# 2_0.net
KiCad netlist of a schematic drawn in Altium Designer
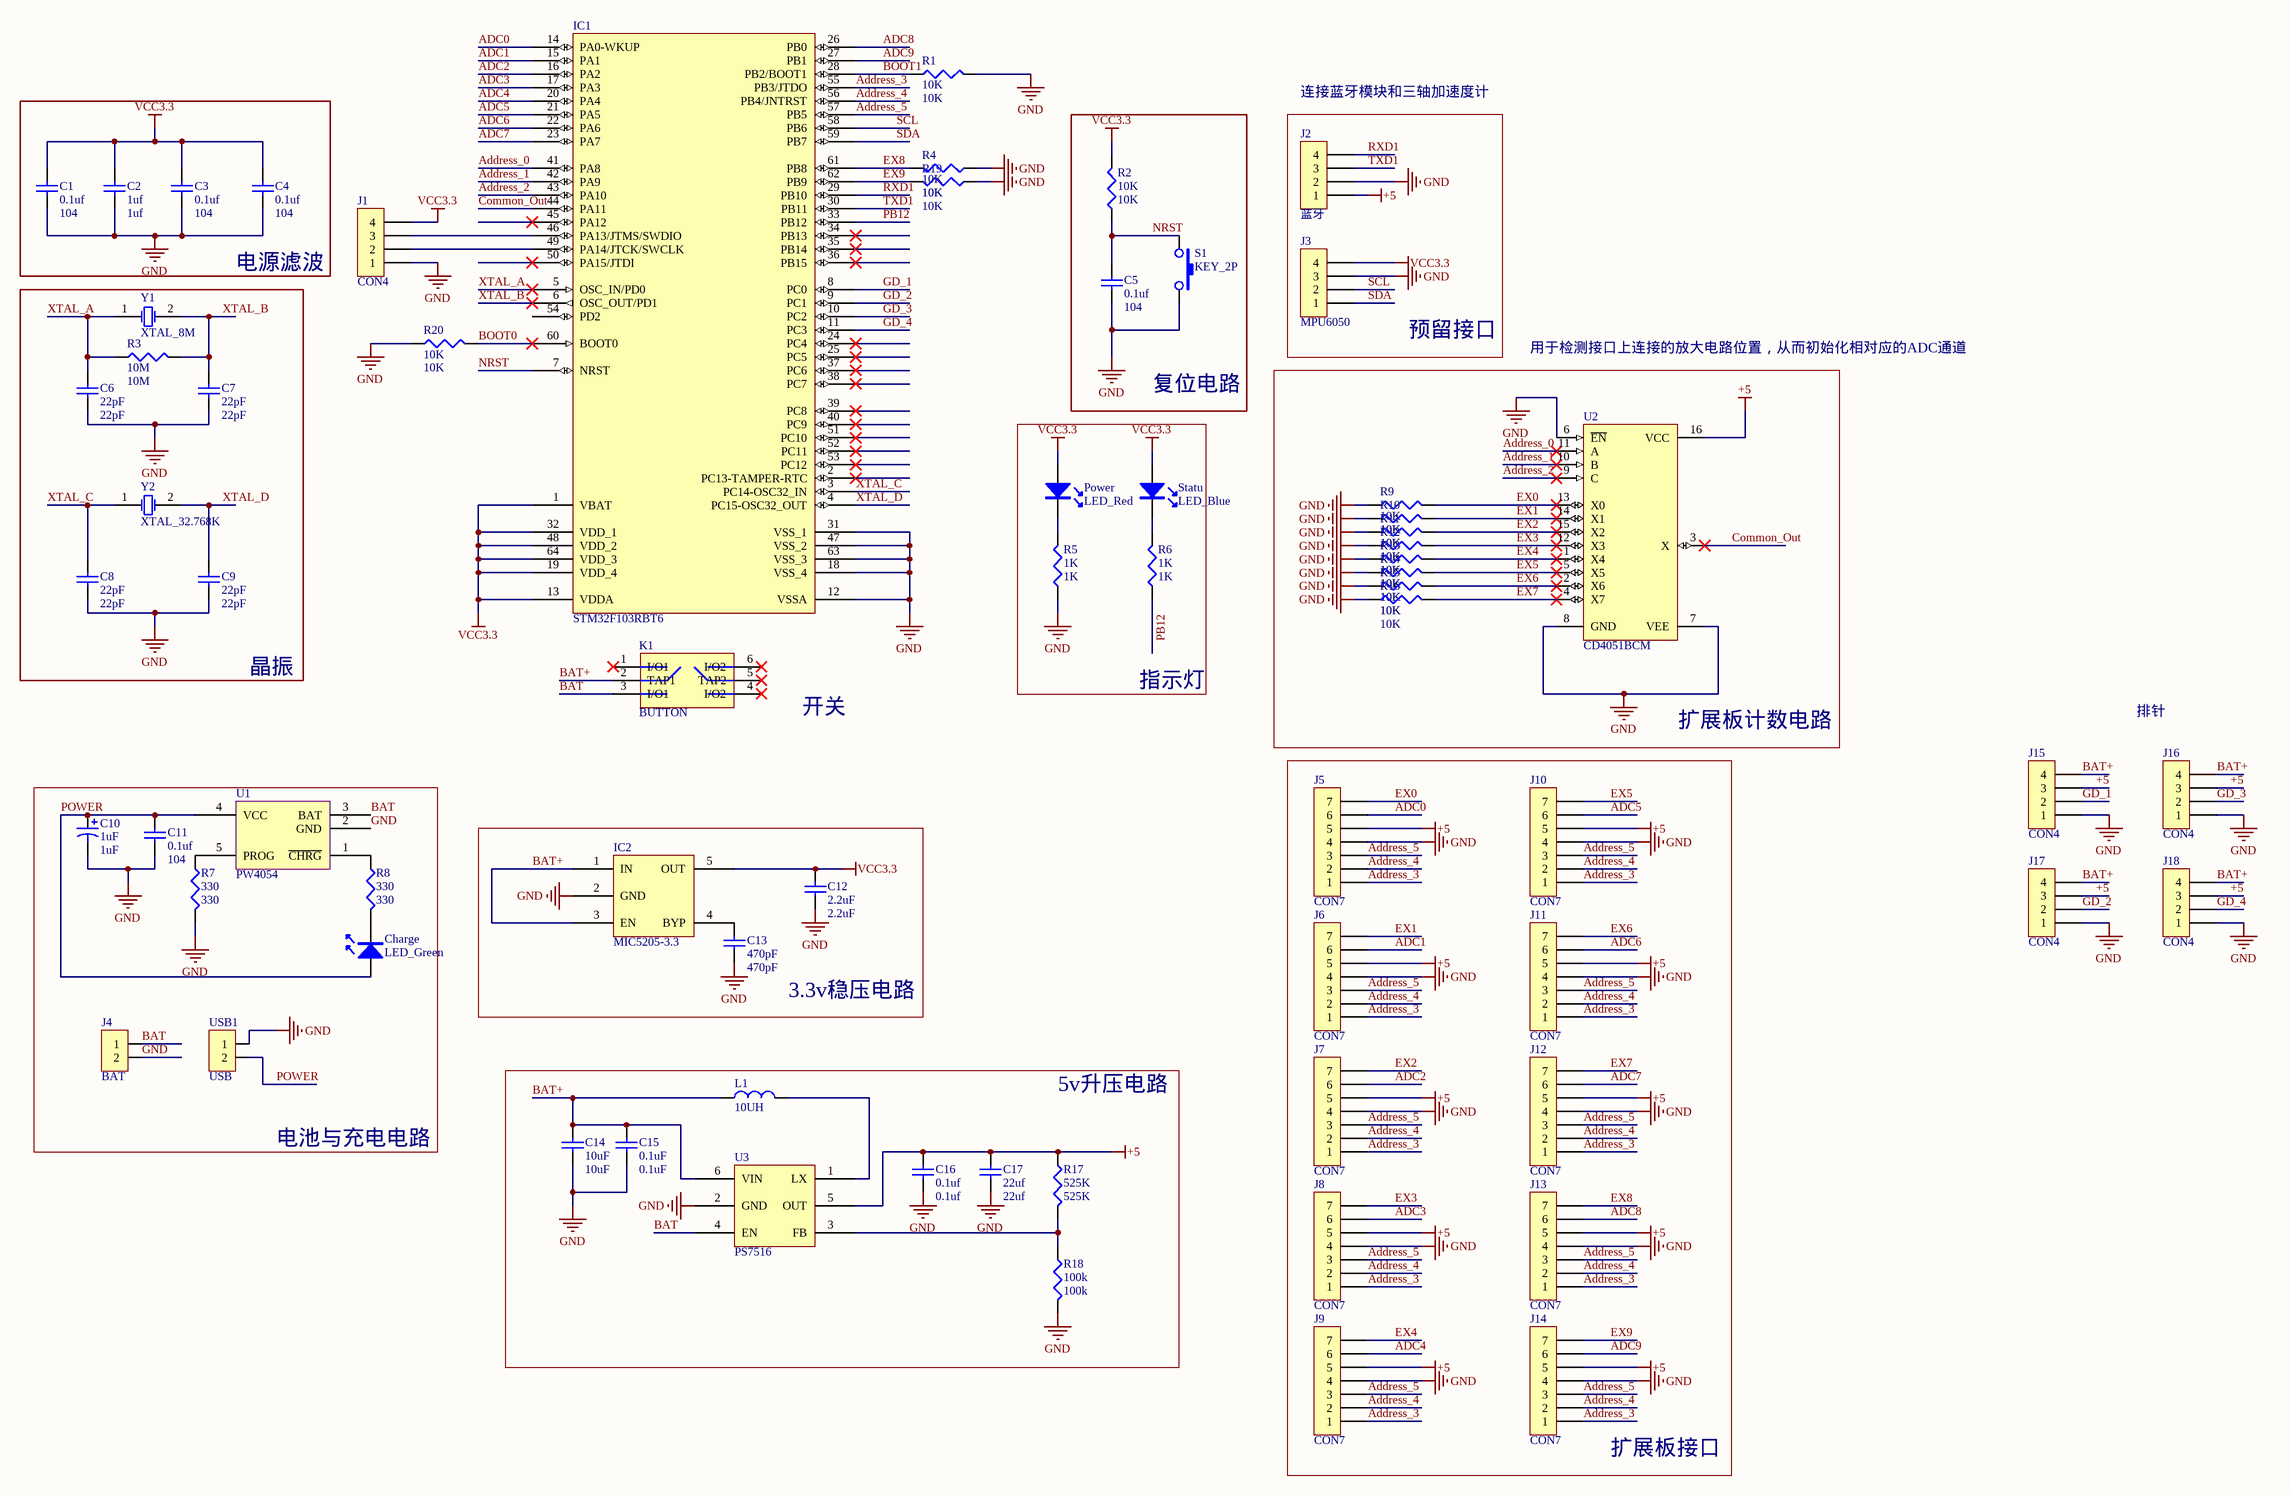
[diagram p0: 主控板原理图2.0.SchDoc]

(export (version "E")
  (design (tool "Eeschema 10.0.6"))
  (components
    (comp (ref "C1")
      (value "0.1uf")
      (footprint "6-0805_L")
      (description "Capacitor (Semiconductor SIM Model)")
      (fields (field (name "ALTIUM_VALUE") "104") (field (name "PUBLISHER") "Altium Limited"))
      (libsource (lib "Miscellaneous Devices") (part "Cap Semi"))
    )
    (comp (ref "C2")
      (value "1uf")
      (footprint "6-0805_L")
      (description "Capacitor (Semiconductor SIM Model)")
      (fields (field (name "ALTIUM_VALUE") "1uf") (field (name "PUBLISHER") "Altium Limited"))
      (libsource (lib "Miscellaneous Devices") (part "Cap Semi"))
    )
    (comp (ref "C3")
      (value "0.1uf")
      (footprint "6-0805_L")
      (description "Capacitor (Semiconductor SIM Model)")
      (fields (field (name "ALTIUM_VALUE") "104") (field (name "PUBLISHER") "Altium Limited"))
      (libsource (lib "Miscellaneous Devices") (part "Cap Semi"))
    )
    (comp (ref "C4")
      (value "0.1uf")
      (footprint "6-0805_L")
      (description "Capacitor (Semiconductor SIM Model)")
      (fields (field (name "ALTIUM_VALUE") "104") (field (name "PUBLISHER") "Altium Limited"))
      (libsource (lib "Miscellaneous Devices") (part "Cap Semi"))
    )
    (comp (ref "C5")
      (value "0.1uf")
      (footprint "6-0805_L")
      (description "Capacitor (Semiconductor SIM Model)")
      (fields (field (name "ALTIUM_VALUE") "104") (field (name "PUBLISHER") "Altium Limited"))
      (libsource (lib "Miscellaneous Devices") (part "Cap Semi"))
    )
    (comp (ref "C6")
      (value "22pF")
      (footprint "6-0805_L")
      (description "Capacitor (Semiconductor SIM Model)")
      (fields (field (name "ALTIUM_VALUE") "22pF") (field (name "PUBLISHER") "Altium Limited"))
      (libsource (lib "Miscellaneous Devices") (part "Cap Semi"))
    )
    (comp (ref "C7")
      (value "22pF")
      (footprint "6-0805_L")
      (description "Capacitor (Semiconductor SIM Model)")
      (fields (field (name "ALTIUM_VALUE") "22pF") (field (name "PUBLISHER") "Altium Limited"))
      (libsource (lib "Miscellaneous Devices") (part "Cap Semi"))
    )
    (comp (ref "C8")
      (value "22pF")
      (footprint "6-0805_L")
      (description "Capacitor (Semiconductor SIM Model)")
      (fields (field (name "ALTIUM_VALUE") "22pF") (field (name "PUBLISHER") "Altium Limited"))
      (libsource (lib "Miscellaneous Devices") (part "Cap Semi"))
    )
    (comp (ref "C9")
      (value "22pF")
      (footprint "6-0805_L")
      (description "Capacitor (Semiconductor SIM Model)")
      (fields (field (name "ALTIUM_VALUE") "22pF") (field (name "PUBLISHER") "Altium Limited"))
      (libsource (lib "Miscellaneous Devices") (part "Cap Semi"))
    )
    (comp (ref "C10")
      (value "1uF")
      (footprint "C0805")
      (description "Polarized Capacitor (Surface Mount)")
      (fields (field (name "ALTIUM_VALUE") "1uF") (field (name "PUBLISHER") "Altium Limited"))
      (libsource (lib "Miscellaneous Devices") (part "Cap Pol3"))
    )
    (comp (ref "C11")
      (value "0.1uf")
      (footprint "6-0805_L")
      (description "Capacitor (Semiconductor SIM Model)")
      (fields (field (name "ALTIUM_VALUE") "104") (field (name "PUBLISHER") "Altium Limited"))
      (libsource (lib "Miscellaneous Devices") (part "Cap Semi"))
    )
    (comp (ref "C12")
      (value "2.2uF")
      (footprint "6-0805_L")
      (description "Capacitor (Semiconductor SIM Model)")
      (fields (field (name "ALTIUM_VALUE") "2.2uF") (field (name "PUBLISHER") "Altium Limited"))
      (libsource (lib "Miscellaneous Devices") (part "Cap Semi"))
    )
    (comp (ref "C13")
      (value "470pF")
      (footprint "6-0805_L")
      (description "Capacitor (Semiconductor SIM Model)")
      (fields (field (name "ALTIUM_VALUE") "470pF") (field (name "PUBLISHER") "Altium Limited"))
      (libsource (lib "Miscellaneous Devices") (part "Cap Semi"))
    )
    (comp (ref "C14")
      (value "10uF")
      (footprint "6-0805_L")
      (description "Capacitor (Semiconductor SIM Model)")
      (fields (field (name "ALTIUM_VALUE") "10uF") (field (name "PUBLISHER") "Altium Limited"))
      (libsource (lib "Miscellaneous Devices") (part "Cap Semi"))
    )
    (comp (ref "C15")
      (value "0.1uF")
      (footprint "6-0805_L")
      (description "Capacitor (Semiconductor SIM Model)")
      (fields (field (name "ALTIUM_VALUE") "0.1uF") (field (name "PUBLISHER") "Altium Limited"))
      (libsource (lib "Miscellaneous Devices") (part "Cap Semi"))
    )
    (comp (ref "C16")
      (value "0.1uf")
      (footprint "6-0805_L")
      (description "Capacitor (Semiconductor SIM Model)")
      (fields (field (name "ALTIUM_VALUE") "0.1uf") (field (name "PUBLISHER") "Altium Limited"))
      (libsource (lib "Miscellaneous Devices") (part "Cap Semi"))
    )
    (comp (ref "C17")
      (value "22uf")
      (footprint "6-0805_L")
      (description "Capacitor (Semiconductor SIM Model)")
      (fields (field (name "ALTIUM_VALUE") "22uf") (field (name "PUBLISHER") "Altium Limited"))
      (libsource (lib "Miscellaneous Devices") (part "Cap Semi"))
    )
    (comp (ref "Charge")
      (value "LED_Green")
      (footprint "6-0805_M")
      (description "LED")
      (libsource (lib "Component") (part "LED"))
    )
    (comp (ref "IC1")
      (value "STM32F103RBT6")
      (footprint "LQFP64_N")
      (description "STM32 ARM-based 32-bit MCU with 128 Kbytes Flash, 64-pin LQFP, Industrial Temperature")
      (fields (field (name "PUBLISHER") "Altium Limited"))
      (libsource (lib "ST Microcontroller 32-Bit STM32") (part "STM32F103RBT6"))
    )
    (comp (ref "IC2")
      (value "MIC5205-3.3")
      (footprint "SOT-23-5")
      (description "稳压")
      (libsource (lib "Chip") (part "MIC5205-3.3"))
    )
    (comp (ref "J1")
      (value "CON4")
      (footprint "HDR1X4")
      (description "连接器")
      (libsource (lib "Connector") (part "CON4"))
    )
    (comp (ref "J2")
      (value "蓝牙")
      (footprint "HDR1X4")
      (description "Connector")
      (libsource (lib "杂元件库") (part "CON4"))
    )
    (comp (ref "J3")
      (value "MPU6050")
      (footprint "HDR1X4")
      (description "Connector")
      (libsource (lib "杂元件库") (part "CON4"))
    )
    (comp (ref "J4")
      (value "BAT")
      (footprint "HDR1X2")
      (description "Conjunctor")
      (libsource (lib "zj") (part "CON2"))
    )
    (comp (ref "J5")
      (value "CON7")
      (footprint "8P软排线")
      (description "Connector")
      (libsource (lib "杂元件库") (part "CON7"))
    )
    (comp (ref "J6")
      (value "CON7")
      (footprint "8P软排线")
      (description "Connector")
      (libsource (lib "杂元件库") (part "CON7"))
    )
    (comp (ref "J7")
      (value "CON7")
      (footprint "8P软排线")
      (description "Connector")
      (libsource (lib "杂元件库") (part "CON7"))
    )
    (comp (ref "J8")
      (value "CON7")
      (footprint "8P软排线")
      (description "Connector")
      (libsource (lib "杂元件库") (part "CON7"))
    )
    (comp (ref "J9")
      (value "CON7")
      (footprint "8P软排线")
      (description "Connector")
      (libsource (lib "杂元件库") (part "CON7"))
    )
    (comp (ref "J10")
      (value "CON7")
      (footprint "8P软排线")
      (description "Connector")
      (libsource (lib "杂元件库") (part "CON7"))
    )
    (comp (ref "J11")
      (value "CON7")
      (footprint "8P软排线")
      (description "Connector")
      (libsource (lib "杂元件库") (part "CON7"))
    )
    (comp (ref "J12")
      (value "CON7")
      (footprint "8P软排线")
      (description "Connector")
      (libsource (lib "杂元件库") (part "CON7"))
    )
    (comp (ref "J13")
      (value "CON7")
      (footprint "8P软排线")
      (description "Connector")
      (libsource (lib "杂元件库") (part "CON7"))
    )
    (comp (ref "J14")
      (value "CON7")
      (footprint "8P软排线")
      (description "Connector")
      (libsource (lib "杂元件库") (part "CON7"))
    )
    (comp (ref "J15") (value "CON4") (description "Connector") (libsource (lib "杂元件库") (part "CON4")))
    (comp (ref "J16") (value "CON4") (description "Connector") (libsource (lib "杂元件库") (part "CON4")))
    (comp (ref "J17") (value "CON4") (description "Connector") (libsource (lib "杂元件库") (part "CON4")))
    (comp (ref "J18") (value "CON4") (description "Connector") (libsource (lib "杂元件库") (part "CON4")))
    (comp (ref "K1")
      (value "BUTTON")
      (footprint "My:switch")
      (description "自锁按键")
      (libsource (lib "Component") (part "BUTTON"))
    )
    (comp (ref "L1")
      (value "10UH")
      (footprint "0850")
      (description "电感")
      (libsource (lib "Component") (part "Inductor"))
    )
    (comp (ref "Power")
      (value "LED_Red")
      (footprint "6-0805_M")
      (description "LED")
      (libsource (lib "Component") (part "LED"))
    )
    (comp (ref "R1")
      (value "10K")
      (footprint "6-0805_L")
      (description "Resistor")
      (fields (field (name "ALTIUM_VALUE") "10K") (field (name "PUBLISHER") "Altium Limited"))
      (libsource (lib "Miscellaneous Devices") (part "Res3"))
    )
    (comp (ref "R2")
      (value "10K")
      (footprint "6-0805_L")
      (description "Resistor")
      (fields (field (name "ALTIUM_VALUE") "10K") (field (name "PUBLISHER") "Altium Limited"))
      (libsource (lib "Miscellaneous Devices") (part "Res3"))
    )
    (comp (ref "R3")
      (value "10M")
      (footprint "6-0805_L")
      (description "Resistor")
      (fields (field (name "ALTIUM_VALUE") "10M") (field (name "PUBLISHER") "Altium Limited"))
      (libsource (lib "Miscellaneous Devices") (part "Res3"))
    )
    (comp (ref "R4")
      (value "10K")
      (footprint "6-0805_L")
      (description "Resistor")
      (fields (field (name "ALTIUM_VALUE") "10K") (field (name "PUBLISHER") "Altium Limited"))
      (libsource (lib "Miscellaneous Devices") (part "Res3"))
    )
    (comp (ref "R5")
      (value "1K")
      (footprint "6-0805_L")
      (description "Resistor")
      (fields (field (name "ALTIUM_VALUE") "1K") (field (name "PUBLISHER") "Altium Limited"))
      (libsource (lib "Miscellaneous Devices") (part "Res3"))
    )
    (comp (ref "R6")
      (value "1K")
      (footprint "6-0805_L")
      (description "Resistor")
      (fields (field (name "ALTIUM_VALUE") "1K") (field (name "PUBLISHER") "Altium Limited"))
      (libsource (lib "Miscellaneous Devices") (part "Res3"))
    )
    (comp (ref "R7")
      (value "330")
      (footprint "6-0805_L")
      (description "Resistor")
      (fields (field (name "ALTIUM_VALUE") "330") (field (name "PUBLISHER") "Altium Limited"))
      (libsource (lib "Miscellaneous Devices") (part "Res3"))
    )
    (comp (ref "R8")
      (value "330")
      (footprint "6-0805_L")
      (description "Resistor")
      (fields (field (name "ALTIUM_VALUE") "330") (field (name "PUBLISHER") "Altium Limited"))
      (libsource (lib "Miscellaneous Devices") (part "Res3"))
    )
    (comp (ref "R9")
      (value "10K")
      (footprint "6-0805_L")
      (description "Resistor")
      (fields (field (name "ALTIUM_VALUE") "10K") (field (name "PUBLISHER") "Altium Limited"))
      (libsource (lib "Miscellaneous Devices") (part "Res3"))
    )
    (comp (ref "R10")
      (value "10K")
      (footprint "6-0805_L")
      (description "Resistor")
      (fields (field (name "ALTIUM_VALUE") "10K") (field (name "PUBLISHER") "Altium Limited"))
      (libsource (lib "Miscellaneous Devices") (part "Res3"))
    )
    (comp (ref "R11")
      (value "10K")
      (footprint "6-0805_L")
      (description "Resistor")
      (fields (field (name "ALTIUM_VALUE") "10K") (field (name "PUBLISHER") "Altium Limited"))
      (libsource (lib "Miscellaneous Devices") (part "Res3"))
    )
    (comp (ref "R12")
      (value "10K")
      (footprint "6-0805_L")
      (description "Resistor")
      (fields (field (name "ALTIUM_VALUE") "10K") (field (name "PUBLISHER") "Altium Limited"))
      (libsource (lib "Miscellaneous Devices") (part "Res3"))
    )
    (comp (ref "R13")
      (value "10K")
      (footprint "6-0805_L")
      (description "Resistor")
      (fields (field (name "ALTIUM_VALUE") "10K") (field (name "PUBLISHER") "Altium Limited"))
      (libsource (lib "Miscellaneous Devices") (part "Res3"))
    )
    (comp (ref "R14")
      (value "10K")
      (footprint "6-0805_L")
      (description "Resistor")
      (fields (field (name "ALTIUM_VALUE") "10K") (field (name "PUBLISHER") "Altium Limited"))
      (libsource (lib "Miscellaneous Devices") (part "Res3"))
    )
    (comp (ref "R15")
      (value "10K")
      (footprint "6-0805_L")
      (description "Resistor")
      (fields (field (name "ALTIUM_VALUE") "10K") (field (name "PUBLISHER") "Altium Limited"))
      (libsource (lib "Miscellaneous Devices") (part "Res3"))
    )
    (comp (ref "R16")
      (value "10K")
      (footprint "6-0805_L")
      (description "Resistor")
      (fields (field (name "ALTIUM_VALUE") "10K") (field (name "PUBLISHER") "Altium Limited"))
      (libsource (lib "Miscellaneous Devices") (part "Res3"))
    )
    (comp (ref "R17")
      (value "525K")
      (footprint "6-0805_L")
      (description "Resistor")
      (fields (field (name "ALTIUM_VALUE") "525K") (field (name "PUBLISHER") "Altium Limited"))
      (libsource (lib "Miscellaneous Devices") (part "Res3"))
    )
    (comp (ref "R18")
      (value "100k")
      (footprint "6-0805_L")
      (description "Resistor")
      (fields (field (name "ALTIUM_VALUE") "100k") (field (name "PUBLISHER") "Altium Limited"))
      (libsource (lib "Miscellaneous Devices") (part "Res3"))
    )
    (comp (ref "R19")
      (value "10K")
      (footprint "6-0805_L")
      (description "Resistor")
      (fields (field (name "ALTIUM_VALUE") "10K") (field (name "PUBLISHER") "Altium Limited"))
      (libsource (lib "Miscellaneous Devices") (part "Res3"))
    )
    (comp (ref "R20")
      (value "10K")
      (footprint "6-0805_L")
      (description "Resistor")
      (fields (field (name "ALTIUM_VALUE") "10K") (field (name "PUBLISHER") "Altium Limited"))
      (libsource (lib "Miscellaneous Devices") (part "Res3"))
    )
    (comp (ref "S1")
      (value "KEY_2P")
      (footprint "My:button")
      (description "轻触按键2P")
      (libsource (lib "Component") (part "KEY_2P"))
    )
    (comp (ref "Statu")
      (value "LED_Blue")
      (footprint "6-0805_M")
      (description "LED")
      (libsource (lib "Component") (part "LED"))
    )
    (comp (ref "U1") (value "PW4054") (footprint "SOT-23-CT5_L") (libsource (lib "Schlib") (part "PW4054")))
    (comp (ref "U2")
      (value "CD4051BCM")
      (footprint "M16A_N")
      (description "8-Channel Analog Multiplexer/Demultiplexer")
      (fields (field (name "PUBLISHER") "Altium Limited"))
      (libsource (lib "altium-import") (part "root_0_CD4051BCM_"))
    )
    (comp (ref "U3")
      (value "PS7516")
      (footprint "SOT23-6_M")
      (libsource (lib "Integrated_Library1") (part "PS7516"))
    )
    (comp (ref "USB1")
      (value "USB")
      (footprint "Type-C")
      (description "Conjunctor")
      (libsource (lib "zj") (part "CON2"))
    )
    (comp (ref "Y1")
      (value "XTAL_8M")
      (footprint "xtal")
      (description "Crystal Oscillator")
      (fields (field (name "PUBLISHER") "Altium Limited"))
      (libsource (lib "Miscellaneous Devices") (part "XTAL"))
    )
    (comp (ref "Y2")
      (value "XTAL_32.768K")
      (footprint "R38")
      (description "Crystal Oscillator")
      (fields (field (name "PUBLISHER") "Altium Limited"))
      (libsource (lib "Miscellaneous Devices") (part "XTAL"))
    )
  )
  (nets
    (net (code "1") (name "+5") (class "Default")
      (node (ref "C16") (pin "2") (pinfunction "2_2") (pintype "passive"))
      (node (ref "C17") (pin "2") (pinfunction "2_2") (pintype "passive"))
      (node (ref "J10") (pin "5") (pinfunction "5_5") (pintype "passive"))
      (node (ref "J11") (pin "5") (pinfunction "5_5") (pintype "passive"))
      (node (ref "J12") (pin "5") (pinfunction "5_5") (pintype "passive"))
      (node (ref "J13") (pin "5") (pinfunction "5_5") (pintype "passive"))
      (node (ref "J14") (pin "5") (pinfunction "5_5") (pintype "passive"))
      (node (ref "J15") (pin "3") (pinfunction "3_3") (pintype "passive"))
      (node (ref "J16") (pin "3") (pinfunction "3_3") (pintype "passive"))
      (node (ref "J17") (pin "3") (pinfunction "3_3") (pintype "passive"))
      (node (ref "J18") (pin "3") (pinfunction "3_3") (pintype "passive"))
      (node (ref "J2") (pin "1") (pinfunction "1_1") (pintype "passive"))
      (node (ref "J5") (pin "5") (pinfunction "5_5") (pintype "passive"))
      (node (ref "J6") (pin "5") (pinfunction "5_5") (pintype "passive"))
      (node (ref "J7") (pin "5") (pinfunction "5_5") (pintype "passive"))
      (node (ref "J8") (pin "5") (pinfunction "5_5") (pintype "passive"))
      (node (ref "J9") (pin "5") (pinfunction "5_5") (pintype "passive"))
      (node (ref "R17") (pin "1") (pinfunction "1_1") (pintype "passive"))
      (node (ref "U2") (pin "16") (pinfunction "VCC_16") (pintype "power_in"))
      (node (ref "U3") (pin "5") (pinfunction "OUT_5") (pintype "passive"))
    )
    (net (code "2") (name "/ADC0") (class "Default")
      (node (ref "IC1") (pin "14") (pinfunction "PA0-WKUP_14") (pintype "bidirectional"))
      (node (ref "J5") (pin "6") (pinfunction "6_6") (pintype "passive"))
    )
    (net (code "3") (name "/ADC1") (class "Default")
      (node (ref "IC1") (pin "15") (pinfunction "PA1_15") (pintype "bidirectional"))
      (node (ref "J6") (pin "6") (pinfunction "6_6") (pintype "passive"))
    )
    (net (code "4") (name "/ADC2") (class "Default")
      (node (ref "IC1") (pin "16") (pinfunction "PA2_16") (pintype "bidirectional"))
      (node (ref "J7") (pin "6") (pinfunction "6_6") (pintype "passive"))
    )
    (net (code "5") (name "/ADC3") (class "Default")
      (node (ref "IC1") (pin "17") (pinfunction "PA3_17") (pintype "bidirectional"))
      (node (ref "J8") (pin "6") (pinfunction "6_6") (pintype "passive"))
    )
    (net (code "6") (name "/ADC4") (class "Default")
      (node (ref "IC1") (pin "20") (pinfunction "PA4_20") (pintype "bidirectional"))
      (node (ref "J9") (pin "6") (pinfunction "6_6") (pintype "passive"))
    )
    (net (code "7") (name "/ADC5") (class "Default")
      (node (ref "IC1") (pin "21") (pinfunction "PA5_21") (pintype "bidirectional"))
      (node (ref "J10") (pin "6") (pinfunction "6_6") (pintype "passive"))
    )
    (net (code "8") (name "/ADC6") (class "Default")
      (node (ref "IC1") (pin "22") (pinfunction "PA6_22") (pintype "bidirectional"))
      (node (ref "J11") (pin "6") (pinfunction "6_6") (pintype "passive"))
    )
    (net (code "9") (name "/ADC7") (class "Default")
      (node (ref "IC1") (pin "23") (pinfunction "PA7_23") (pintype "bidirectional"))
      (node (ref "J12") (pin "6") (pinfunction "6_6") (pintype "passive"))
    )
    (net (code "10") (name "/ADC8") (class "Default")
      (node (ref "IC1") (pin "26") (pinfunction "PB0_26") (pintype "bidirectional"))
      (node (ref "J13") (pin "6") (pinfunction "6_6") (pintype "passive"))
    )
    (net (code "11") (name "/ADC9") (class "Default")
      (node (ref "IC1") (pin "27") (pinfunction "PB1_27") (pintype "bidirectional"))
      (node (ref "J14") (pin "6") (pinfunction "6_6") (pintype "passive"))
    )
    (net (code "12") (name "/Address_0") (class "Default")
      (node (ref "IC1") (pin "41") (pinfunction "PA8_41") (pintype "bidirectional"))
      (node (ref "U2") (pin "11") (pinfunction "A_11") (pintype "input"))
    )
    (net (code "13") (name "/Address_1") (class "Default")
      (node (ref "IC1") (pin "42") (pinfunction "PA9_42") (pintype "bidirectional"))
      (node (ref "U2") (pin "10") (pinfunction "B_10") (pintype "input"))
    )
    (net (code "14") (name "/Address_2") (class "Default")
      (node (ref "IC1") (pin "43") (pinfunction "PA10_43") (pintype "bidirectional"))
      (node (ref "U2") (pin "9") (pinfunction "C_9") (pintype "input"))
    )
    (net (code "15") (name "/Address_3") (class "Default")
      (node (ref "IC1") (pin "55") (pinfunction "PB3/JTDO_55") (pintype "bidirectional"))
      (node (ref "J10") (pin "1") (pinfunction "1_1") (pintype "passive"))
      (node (ref "J11") (pin "1") (pinfunction "1_1") (pintype "passive"))
      (node (ref "J12") (pin "1") (pinfunction "1_1") (pintype "passive"))
      (node (ref "J13") (pin "1") (pinfunction "1_1") (pintype "passive"))
      (node (ref "J14") (pin "1") (pinfunction "1_1") (pintype "passive"))
      (node (ref "J5") (pin "1") (pinfunction "1_1") (pintype "passive"))
      (node (ref "J6") (pin "1") (pinfunction "1_1") (pintype "passive"))
      (node (ref "J7") (pin "1") (pinfunction "1_1") (pintype "passive"))
      (node (ref "J8") (pin "1") (pinfunction "1_1") (pintype "passive"))
      (node (ref "J9") (pin "1") (pinfunction "1_1") (pintype "passive"))
    )
    (net (code "16") (name "/Address_4") (class "Default")
      (node (ref "IC1") (pin "56") (pinfunction "PB4/JNTRST_56") (pintype "bidirectional"))
      (node (ref "J10") (pin "2") (pinfunction "2_2") (pintype "passive"))
      (node (ref "J11") (pin "2") (pinfunction "2_2") (pintype "passive"))
      (node (ref "J12") (pin "2") (pinfunction "2_2") (pintype "passive"))
      (node (ref "J13") (pin "2") (pinfunction "2_2") (pintype "passive"))
      (node (ref "J14") (pin "2") (pinfunction "2_2") (pintype "passive"))
      (node (ref "J5") (pin "2") (pinfunction "2_2") (pintype "passive"))
      (node (ref "J6") (pin "2") (pinfunction "2_2") (pintype "passive"))
      (node (ref "J7") (pin "2") (pinfunction "2_2") (pintype "passive"))
      (node (ref "J8") (pin "2") (pinfunction "2_2") (pintype "passive"))
      (node (ref "J9") (pin "2") (pinfunction "2_2") (pintype "passive"))
    )
    (net (code "17") (name "/Address_5") (class "Default")
      (node (ref "IC1") (pin "57") (pinfunction "PB5_57") (pintype "bidirectional"))
      (node (ref "J10") (pin "3") (pinfunction "3_3") (pintype "passive"))
      (node (ref "J11") (pin "3") (pinfunction "3_3") (pintype "passive"))
      (node (ref "J12") (pin "3") (pinfunction "3_3") (pintype "passive"))
      (node (ref "J13") (pin "3") (pinfunction "3_3") (pintype "passive"))
      (node (ref "J14") (pin "3") (pinfunction "3_3") (pintype "passive"))
      (node (ref "J5") (pin "3") (pinfunction "3_3") (pintype "passive"))
      (node (ref "J6") (pin "3") (pinfunction "3_3") (pintype "passive"))
      (node (ref "J7") (pin "3") (pinfunction "3_3") (pintype "passive"))
      (node (ref "J8") (pin "3") (pinfunction "3_3") (pintype "passive"))
      (node (ref "J9") (pin "3") (pinfunction "3_3") (pintype "passive"))
    )
    (net (code "18") (name "/BAT") (class "Default")
      (node (ref "J4") (pin "1") (pinfunction "1_1") (pintype "passive"))
      (node (ref "K1") (pin "3") (pinfunction "I/O1_3") (pintype "passive"))
      (node (ref "U1") (pin "3") (pinfunction "BAT_3") (pintype "passive"))
      (node (ref "U3") (pin "4") (pinfunction "EN_4") (pintype "passive"))
    )
    (net (code "19") (name "/BAT+") (class "Default")
      (node (ref "C14") (pin "2") (pinfunction "2_2") (pintype "passive"))
      (node (ref "C15") (pin "2") (pinfunction "2_2") (pintype "passive"))
      (node (ref "IC2") (pin "1") (pinfunction "IN_1") (pintype "passive"))
      (node (ref "IC2") (pin "3") (pinfunction "EN_3") (pintype "passive"))
      (node (ref "J15") (pin "4") (pinfunction "4_4") (pintype "passive"))
      (node (ref "J16") (pin "4") (pinfunction "4_4") (pintype "passive"))
      (node (ref "J17") (pin "4") (pinfunction "4_4") (pintype "passive"))
      (node (ref "J18") (pin "4") (pinfunction "4_4") (pintype "passive"))
      (node (ref "K1") (pin "2") (pinfunction "TAP1_2") (pintype "passive"))
      (node (ref "L1") (pin "1") (pinfunction "1_1") (pintype "passive"))
      (node (ref "U3") (pin "6") (pinfunction "VIN_6") (pintype "passive"))
    )
    (net (code "20") (name "/BOOT0") (class "Default")
      (node (ref "IC1") (pin "60") (pinfunction "BOOT0_60") (pintype "input"))
      (node (ref "R20") (pin "2") (pinfunction "2_2") (pintype "passive"))
    )
    (net (code "21") (name "/BOOT1") (class "Default")
      (node (ref "IC1") (pin "28") (pinfunction "PB2/BOOT1_28") (pintype "bidirectional"))
      (node (ref "R1") (pin "1") (pinfunction "1_1") (pintype "passive"))
    )
    (net (code "22") (name "/Common_Out") (class "Default")
      (node (ref "IC1") (pin "44") (pinfunction "PA11_44") (pintype "bidirectional"))
      (node (ref "U2") (pin "3") (pinfunction "X_3") (pintype "bidirectional"))
    )
    (net (code "23") (name "/EX0") (class "Default")
      (node (ref "J5") (pin "7") (pinfunction "7_7") (pintype "passive"))
      (node (ref "R9") (pin "2") (pinfunction "2_2") (pintype "passive"))
      (node (ref "U2") (pin "13") (pinfunction "X0_13") (pintype "bidirectional"))
    )
    (net (code "24") (name "/EX1") (class "Default")
      (node (ref "J6") (pin "7") (pinfunction "7_7") (pintype "passive"))
      (node (ref "R10") (pin "2") (pinfunction "2_2") (pintype "passive"))
      (node (ref "U2") (pin "14") (pinfunction "X1_14") (pintype "bidirectional"))
    )
    (net (code "25") (name "/EX2") (class "Default")
      (node (ref "J7") (pin "7") (pinfunction "7_7") (pintype "passive"))
      (node (ref "R11") (pin "2") (pinfunction "2_2") (pintype "passive"))
      (node (ref "U2") (pin "15") (pinfunction "X2_15") (pintype "bidirectional"))
    )
    (net (code "26") (name "/EX3") (class "Default")
      (node (ref "J8") (pin "7") (pinfunction "7_7") (pintype "passive"))
      (node (ref "R12") (pin "2") (pinfunction "2_2") (pintype "passive"))
      (node (ref "U2") (pin "12") (pinfunction "X3_12") (pintype "bidirectional"))
    )
    (net (code "27") (name "/EX4") (class "Default")
      (node (ref "J9") (pin "7") (pinfunction "7_7") (pintype "passive"))
      (node (ref "R13") (pin "2") (pinfunction "2_2") (pintype "passive"))
      (node (ref "U2") (pin "1") (pinfunction "X4_1") (pintype "bidirectional"))
    )
    (net (code "28") (name "/EX5") (class "Default")
      (node (ref "J10") (pin "7") (pinfunction "7_7") (pintype "passive"))
      (node (ref "R14") (pin "2") (pinfunction "2_2") (pintype "passive"))
      (node (ref "U2") (pin "5") (pinfunction "X5_5") (pintype "bidirectional"))
    )
    (net (code "29") (name "/EX6") (class "Default")
      (node (ref "J11") (pin "7") (pinfunction "7_7") (pintype "passive"))
      (node (ref "R15") (pin "2") (pinfunction "2_2") (pintype "passive"))
      (node (ref "U2") (pin "2") (pinfunction "X6_2") (pintype "bidirectional"))
    )
    (net (code "30") (name "/EX7") (class "Default")
      (node (ref "J12") (pin "7") (pinfunction "7_7") (pintype "passive"))
      (node (ref "R16") (pin "2") (pinfunction "2_2") (pintype "passive"))
      (node (ref "U2") (pin "4") (pinfunction "X7_4") (pintype "bidirectional"))
    )
    (net (code "31") (name "/EX8") (class "Default")
      (node (ref "IC1") (pin "61") (pinfunction "PB8_61") (pintype "bidirectional"))
      (node (ref "J13") (pin "7") (pinfunction "7_7") (pintype "passive"))
      (node (ref "R4") (pin "2") (pinfunction "2_2") (pintype "passive"))
    )
    (net (code "32") (name "/EX9") (class "Default")
      (node (ref "IC1") (pin "62") (pinfunction "PB9_62") (pintype "bidirectional"))
      (node (ref "J14") (pin "7") (pinfunction "7_7") (pintype "passive"))
      (node (ref "R19") (pin "2") (pinfunction "2_2") (pintype "passive"))
    )
    (net (code "33") (name "/GD_1") (class "Default")
      (node (ref "IC1") (pin "8") (pinfunction "PC0_8") (pintype "bidirectional"))
      (node (ref "J15") (pin "2") (pinfunction "2_2") (pintype "passive"))
    )
    (net (code "34") (name "/GD_2") (class "Default")
      (node (ref "IC1") (pin "9") (pinfunction "PC1_9") (pintype "bidirectional"))
      (node (ref "J17") (pin "2") (pinfunction "2_2") (pintype "passive"))
    )
    (net (code "35") (name "/GD_3") (class "Default")
      (node (ref "IC1") (pin "10") (pinfunction "PC2_10") (pintype "bidirectional"))
      (node (ref "J16") (pin "2") (pinfunction "2_2") (pintype "passive"))
    )
    (net (code "36") (name "/GD_4") (class "Default")
      (node (ref "IC1") (pin "11") (pinfunction "PC3_11") (pintype "bidirectional"))
      (node (ref "J18") (pin "2") (pinfunction "2_2") (pintype "passive"))
    )
    (net (code "37") (name "/NRST") (class "Default")
      (node (ref "C5") (pin "2") (pinfunction "2_2") (pintype "passive"))
      (node (ref "IC1") (pin "7") (pinfunction "NRST_7") (pintype "bidirectional"))
      (node (ref "R2") (pin "1") (pinfunction "1_1") (pintype "passive"))
      (node (ref "S1") (pin "1") (pinfunction "1_1") (pintype "passive"))
    )
    (net (code "38") (name "/PB12") (class "Default")
      (node (ref "IC1") (pin "33") (pinfunction "PB12_33") (pintype "bidirectional"))
      (node (ref "R6") (pin "1") (pinfunction "1_1") (pintype "passive"))
    )
    (net (code "39") (name "/POWER") (class "Default")
      (node (ref "C10") (pin "1") (pinfunction "1_1") (pintype "passive"))
      (node (ref "C11") (pin "2") (pinfunction "2_2") (pintype "passive"))
      (node (ref "Charge") (pin "1") (pinfunction "1_1") (pintype "passive"))
      (node (ref "U1") (pin "4") (pinfunction "VCC_4") (pintype "passive"))
      (node (ref "USB1") (pin "2") (pinfunction "2_2") (pintype "passive"))
    )
    (net (code "40") (name "/RXD1") (class "Default")
      (node (ref "IC1") (pin "29") (pinfunction "PB10_29") (pintype "bidirectional"))
      (node (ref "J2") (pin "4") (pinfunction "4_4") (pintype "passive"))
    )
    (net (code "41") (name "/SCL") (class "Default")
      (node (ref "IC1") (pin "58") (pinfunction "PB6_58") (pintype "bidirectional"))
      (node (ref "J3") (pin "2") (pinfunction "2_2") (pintype "passive"))
    )
    (net (code "42") (name "/SDA") (class "Default")
      (node (ref "IC1") (pin "59") (pinfunction "PB7_59") (pintype "bidirectional"))
      (node (ref "J3") (pin "1") (pinfunction "1_1") (pintype "passive"))
    )
    (net (code "43") (name "/TXD1") (class "Default")
      (node (ref "IC1") (pin "30") (pinfunction "PB11_30") (pintype "bidirectional"))
      (node (ref "J2") (pin "3") (pinfunction "3_3") (pintype "passive"))
    )
    (net (code "44") (name "/XTAL_A") (class "Default")
      (node (ref "C6") (pin "2") (pinfunction "2_2") (pintype "passive"))
      (node (ref "IC1") (pin "5") (pinfunction "OSC_IN/PD0_5") (pintype "input"))
      (node (ref "R3") (pin "1") (pinfunction "1_1") (pintype "passive"))
      (node (ref "Y1") (pin "1") (pinfunction "OSC1_1") (pintype "passive"))
    )
    (net (code "45") (name "/XTAL_B") (class "Default")
      (node (ref "C7") (pin "2") (pinfunction "2_2") (pintype "passive"))
      (node (ref "IC1") (pin "6") (pinfunction "OSC_OUT/PD1_6") (pintype "output"))
      (node (ref "R3") (pin "2") (pinfunction "2_2") (pintype "passive"))
      (node (ref "Y1") (pin "2") (pinfunction "OSC2_2") (pintype "passive"))
    )
    (net (code "46") (name "/XTAL_C") (class "Default")
      (node (ref "C8") (pin "2") (pinfunction "2_2") (pintype "passive"))
      (node (ref "IC1") (pin "3") (pinfunction "PC14-OSC32_IN_3") (pintype "bidirectional"))
      (node (ref "Y2") (pin "1") (pinfunction "OSC1_1") (pintype "passive"))
    )
    (net (code "47") (name "/XTAL_D") (class "Default")
      (node (ref "C9") (pin "2") (pinfunction "2_2") (pintype "passive"))
      (node (ref "IC1") (pin "4") (pinfunction "PC15-OSC32_OUT_4") (pintype "bidirectional"))
      (node (ref "Y2") (pin "2") (pinfunction "OSC2_2") (pintype "passive"))
    )
    (net (code "48") (name "GND") (class "Default")
      (node (ref "C1") (pin "1") (pinfunction "1_1") (pintype "passive"))
      (node (ref "C10") (pin "2") (pinfunction "2_2") (pintype "passive"))
      (node (ref "C11") (pin "1") (pinfunction "1_1") (pintype "passive"))
      (node (ref "C12") (pin "1") (pinfunction "1_1") (pintype "passive"))
      (node (ref "C13") (pin "1") (pinfunction "1_1") (pintype "passive"))
      (node (ref "C14") (pin "1") (pinfunction "1_1") (pintype "passive"))
      (node (ref "C15") (pin "1") (pinfunction "1_1") (pintype "passive"))
      (node (ref "C16") (pin "1") (pinfunction "1_1") (pintype "passive"))
      (node (ref "C17") (pin "1") (pinfunction "1_1") (pintype "passive"))
      (node (ref "C2") (pin "1") (pinfunction "1_1") (pintype "passive"))
      (node (ref "C3") (pin "1") (pinfunction "1_1") (pintype "passive"))
      (node (ref "C4") (pin "1") (pinfunction "1_1") (pintype "passive"))
      (node (ref "C5") (pin "1") (pinfunction "1_1") (pintype "passive"))
      (node (ref "C6") (pin "1") (pinfunction "1_1") (pintype "passive"))
      (node (ref "C7") (pin "1") (pinfunction "1_1") (pintype "passive"))
      (node (ref "C8") (pin "1") (pinfunction "1_1") (pintype "passive"))
      (node (ref "C9") (pin "1") (pinfunction "1_1") (pintype "passive"))
      (node (ref "IC1") (pin "12") (pinfunction "VSSA_12") (pintype "power_in"))
      (node (ref "IC1") (pin "18") (pinfunction "VSS_4_18") (pintype "power_in"))
      (node (ref "IC1") (pin "31") (pinfunction "VSS_1_31") (pintype "power_in"))
      (node (ref "IC1") (pin "47") (pinfunction "VSS_2_47") (pintype "power_in"))
      (node (ref "IC1") (pin "63") (pinfunction "VSS_3_63") (pintype "power_in"))
      (node (ref "IC2") (pin "2") (pinfunction "GND_2") (pintype "passive"))
      (node (ref "J1") (pin "1") (pinfunction "1_1") (pintype "passive"))
      (node (ref "J10") (pin "4") (pinfunction "4_4") (pintype "passive"))
      (node (ref "J11") (pin "4") (pinfunction "4_4") (pintype "passive"))
      (node (ref "J12") (pin "4") (pinfunction "4_4") (pintype "passive"))
      (node (ref "J13") (pin "4") (pinfunction "4_4") (pintype "passive"))
      (node (ref "J14") (pin "4") (pinfunction "4_4") (pintype "passive"))
      (node (ref "J15") (pin "1") (pinfunction "1_1") (pintype "passive"))
      (node (ref "J16") (pin "1") (pinfunction "1_1") (pintype "passive"))
      (node (ref "J17") (pin "1") (pinfunction "1_1") (pintype "passive"))
      (node (ref "J18") (pin "1") (pinfunction "1_1") (pintype "passive"))
      (node (ref "J2") (pin "2") (pinfunction "2_2") (pintype "passive"))
      (node (ref "J3") (pin "3") (pinfunction "3_3") (pintype "passive"))
      (node (ref "J4") (pin "2") (pinfunction "2_2") (pintype "passive"))
      (node (ref "J5") (pin "4") (pinfunction "4_4") (pintype "passive"))
      (node (ref "J6") (pin "4") (pinfunction "4_4") (pintype "passive"))
      (node (ref "J7") (pin "4") (pinfunction "4_4") (pintype "passive"))
      (node (ref "J8") (pin "4") (pinfunction "4_4") (pintype "passive"))
      (node (ref "J9") (pin "4") (pinfunction "4_4") (pintype "passive"))
      (node (ref "R1") (pin "2") (pinfunction "2_2") (pintype "passive"))
      (node (ref "R10") (pin "1") (pinfunction "1_1") (pintype "passive"))
      (node (ref "R11") (pin "1") (pinfunction "1_1") (pintype "passive"))
      (node (ref "R12") (pin "1") (pinfunction "1_1") (pintype "passive"))
      (node (ref "R13") (pin "1") (pinfunction "1_1") (pintype "passive"))
      (node (ref "R14") (pin "1") (pinfunction "1_1") (pintype "passive"))
      (node (ref "R15") (pin "1") (pinfunction "1_1") (pintype "passive"))
      (node (ref "R16") (pin "1") (pinfunction "1_1") (pintype "passive"))
      (node (ref "R18") (pin "2") (pinfunction "2_2") (pintype "passive"))
      (node (ref "R19") (pin "1") (pinfunction "1_1") (pintype "passive"))
      (node (ref "R20") (pin "1") (pinfunction "1_1") (pintype "passive"))
      (node (ref "R4") (pin "1") (pinfunction "1_1") (pintype "passive"))
      (node (ref "R5") (pin "1") (pinfunction "1_1") (pintype "passive"))
      (node (ref "R7") (pin "2") (pinfunction "2_2") (pintype "passive"))
      (node (ref "R9") (pin "1") (pinfunction "1_1") (pintype "passive"))
      (node (ref "S1") (pin "2") (pinfunction "2_2") (pintype "passive"))
      (node (ref "U1") (pin "2") (pinfunction "GND_2") (pintype "passive"))
      (node (ref "U2") (pin "6") (pinfunction "~{EN}_6") (pintype "input"))
      (node (ref "U2") (pin "7") (pinfunction "VEE_7") (pintype "power_in"))
      (node (ref "U2") (pin "8") (pinfunction "GND_8") (pintype "power_in"))
      (node (ref "U3") (pin "2") (pinfunction "GND_2") (pintype "passive"))
      (node (ref "USB1") (pin "1") (pinfunction "1_1") (pintype "passive"))
    )
    (net (code "49") (name "Net-(Charge-Pad2)") (class "Default")
      (node (ref "Charge") (pin "2") (pinfunction "2_2") (pintype "passive"))
      (node (ref "R8") (pin "2") (pinfunction "2_2") (pintype "passive"))
    )
    (net (code "50") (name "Net-(IC1-PA13{slash}JTMS{slash}SWDIO)") (class "Default")
      (node (ref "IC1") (pin "46") (pinfunction "PA13/JTMS/SWDIO_46") (pintype "bidirectional"))
      (node (ref "J1") (pin "3") (pinfunction "3_3") (pintype "passive"))
    )
    (net (code "51") (name "Net-(IC1-PA14{slash}JTCK{slash}SWCLK)") (class "Default")
      (node (ref "IC1") (pin "49") (pinfunction "PA14/JTCK/SWCLK_49") (pintype "bidirectional"))
      (node (ref "J1") (pin "2") (pinfunction "2_2") (pintype "passive"))
    )
    (net (code "52") (name "Net-(IC2-BYP)") (class "Default")
      (node (ref "C13") (pin "2") (pinfunction "2_2") (pintype "passive"))
      (node (ref "IC2") (pin "4") (pinfunction "BYP_4") (pintype "passive"))
    )
    (net (code "53") (name "Net-(Power-Pad2)") (class "Default")
      (node (ref "Power") (pin "2") (pinfunction "2_2") (pintype "passive"))
      (node (ref "R5") (pin "2") (pinfunction "2_2") (pintype "passive"))
    )
    (net (code "54") (name "Net-(R6-Pad2)") (class "Default")
      (node (ref "R6") (pin "2") (pinfunction "2_2") (pintype "passive"))
      (node (ref "Statu") (pin "2") (pinfunction "2_2") (pintype "passive"))
    )
    (net (code "55") (name "Net-(U1-PROG)") (class "Default")
      (node (ref "R7") (pin "1") (pinfunction "1_1") (pintype "passive"))
      (node (ref "U1") (pin "5") (pinfunction "PROG_5") (pintype "passive"))
    )
    (net (code "56") (name "Net-(U1-~{CHRG})") (class "Default")
      (node (ref "R8") (pin "1") (pinfunction "1_1") (pintype "passive"))
      (node (ref "U1") (pin "1") (pinfunction "~{CHRG}_1") (pintype "passive"))
    )
    (net (code "57") (name "Net-(U3-FB)") (class "Default")
      (node (ref "R17") (pin "2") (pinfunction "2_2") (pintype "passive"))
      (node (ref "R18") (pin "1") (pinfunction "1_1") (pintype "passive"))
      (node (ref "U3") (pin "3") (pinfunction "FB_3") (pintype "passive"))
    )
    (net (code "58") (name "Net-(U3-LX)") (class "Default")
      (node (ref "L1") (pin "2") (pinfunction "2_2") (pintype "passive"))
      (node (ref "U3") (pin "1") (pinfunction "LX_1") (pintype "passive"))
    )
    (net (code "59") (name "VCC3.3") (class "Default")
      (node (ref "C1") (pin "2") (pinfunction "2_2") (pintype "passive"))
      (node (ref "C12") (pin "2") (pinfunction "2_2") (pintype "passive"))
      (node (ref "C2") (pin "2") (pinfunction "2_2") (pintype "passive"))
      (node (ref "C3") (pin "2") (pinfunction "2_2") (pintype "passive"))
      (node (ref "C4") (pin "2") (pinfunction "2_2") (pintype "passive"))
      (node (ref "IC1") (pin "1") (pinfunction "VBAT_1") (pintype "power_in"))
      (node (ref "IC1") (pin "13") (pinfunction "VDDA_13") (pintype "power_in"))
      (node (ref "IC1") (pin "19") (pinfunction "VDD_4_19") (pintype "power_in"))
      (node (ref "IC1") (pin "32") (pinfunction "VDD_1_32") (pintype "power_in"))
      (node (ref "IC1") (pin "48") (pinfunction "VDD_2_48") (pintype "power_in"))
      (node (ref "IC1") (pin "64") (pinfunction "VDD_3_64") (pintype "power_in"))
      (node (ref "IC2") (pin "5") (pinfunction "OUT_5") (pintype "passive"))
      (node (ref "J1") (pin "4") (pinfunction "4_4") (pintype "passive"))
      (node (ref "J3") (pin "4") (pinfunction "4_4") (pintype "passive"))
      (node (ref "Power") (pin "1") (pinfunction "1_1") (pintype "passive"))
      (node (ref "R2") (pin "2") (pinfunction "2_2") (pintype "passive"))
      (node (ref "Statu") (pin "1") (pinfunction "1_1") (pintype "passive"))
    )
    (net (code "60") (name "unconnected-(IC1-PA12-Pad45)") (class "Default")
      (node (ref "IC1") (pin "45") (pinfunction "PA12_45") (pintype "bidirectional+no_connect"))
    )
    (net (code "61") (name "unconnected-(IC1-PA15{slash}JTDI-Pad50)") (class "Default")
      (node (ref "IC1") (pin "50") (pinfunction "PA15/JTDI_50") (pintype "bidirectional+no_connect"))
    )
    (net (code "62") (name "unconnected-(IC1-PB13-Pad34)") (class "Default")
      (node (ref "IC1") (pin "34") (pinfunction "PB13_34") (pintype "bidirectional+no_connect"))
    )
    (net (code "63") (name "unconnected-(IC1-PB14-Pad35)") (class "Default")
      (node (ref "IC1") (pin "35") (pinfunction "PB14_35") (pintype "bidirectional+no_connect"))
    )
    (net (code "64") (name "unconnected-(IC1-PB15-Pad36)") (class "Default")
      (node (ref "IC1") (pin "36") (pinfunction "PB15_36") (pintype "bidirectional+no_connect"))
    )
    (net (code "65") (name "unconnected-(IC1-PC4-Pad24)") (class "Default")
      (node (ref "IC1") (pin "24") (pinfunction "PC4_24") (pintype "bidirectional+no_connect"))
    )
    (net (code "66") (name "unconnected-(IC1-PC5-Pad25)") (class "Default")
      (node (ref "IC1") (pin "25") (pinfunction "PC5_25") (pintype "bidirectional+no_connect"))
    )
    (net (code "67") (name "unconnected-(IC1-PC6-Pad37)") (class "Default")
      (node (ref "IC1") (pin "37") (pinfunction "PC6_37") (pintype "bidirectional+no_connect"))
    )
    (net (code "68") (name "unconnected-(IC1-PC7-Pad38)") (class "Default")
      (node (ref "IC1") (pin "38") (pinfunction "PC7_38") (pintype "bidirectional+no_connect"))
    )
    (net (code "69") (name "unconnected-(IC1-PC8-Pad39)") (class "Default")
      (node (ref "IC1") (pin "39") (pinfunction "PC8_39") (pintype "bidirectional+no_connect"))
    )
    (net (code "70") (name "unconnected-(IC1-PC9-Pad40)") (class "Default")
      (node (ref "IC1") (pin "40") (pinfunction "PC9_40") (pintype "bidirectional+no_connect"))
    )
    (net (code "71") (name "unconnected-(IC1-PC10-Pad51)") (class "Default")
      (node (ref "IC1") (pin "51") (pinfunction "PC10_51") (pintype "bidirectional+no_connect"))
    )
    (net (code "72") (name "unconnected-(IC1-PC11-Pad52)") (class "Default")
      (node (ref "IC1") (pin "52") (pinfunction "PC11_52") (pintype "bidirectional+no_connect"))
    )
    (net (code "73") (name "unconnected-(IC1-PC12-Pad53)") (class "Default")
      (node (ref "IC1") (pin "53") (pinfunction "PC12_53") (pintype "bidirectional+no_connect"))
    )
    (net (code "74") (name "unconnected-(IC1-PC13-TAMPER-RTC-Pad2)") (class "Default")
      (node (ref "IC1") (pin "2") (pinfunction "PC13-TAMPER-RTC_2") (pintype "bidirectional+no_connect"))
    )
    (net (code "75") (name "unconnected-(IC1-PD2-Pad54)") (class "Default")
      (node (ref "IC1") (pin "54") (pinfunction "PD2_54") (pintype "bidirectional"))
    )
    (net (code "76") (name "unconnected-(K1-I{slash}O1-Pad1)") (class "Default")
      (node (ref "K1") (pin "1") (pinfunction "I/O1_1") (pintype "passive+no_connect"))
    )
    (net (code "77") (name "unconnected-(K1-I{slash}O2-Pad4)") (class "Default")
      (node (ref "K1") (pin "4") (pinfunction "I/O2_4") (pintype "passive+no_connect"))
    )
    (net (code "78") (name "unconnected-(K1-I{slash}O2-Pad6)") (class "Default")
      (node (ref "K1") (pin "6") (pinfunction "I/O2_6") (pintype "passive+no_connect"))
    )
    (net (code "79") (name "unconnected-(K1-TAP2-Pad5)") (class "Default")
      (node (ref "K1") (pin "5") (pinfunction "TAP2_5") (pintype "passive+no_connect"))
    )
  )
)
